# servo_1.net
KiCad netlist of a schematic drawn in EAGLE
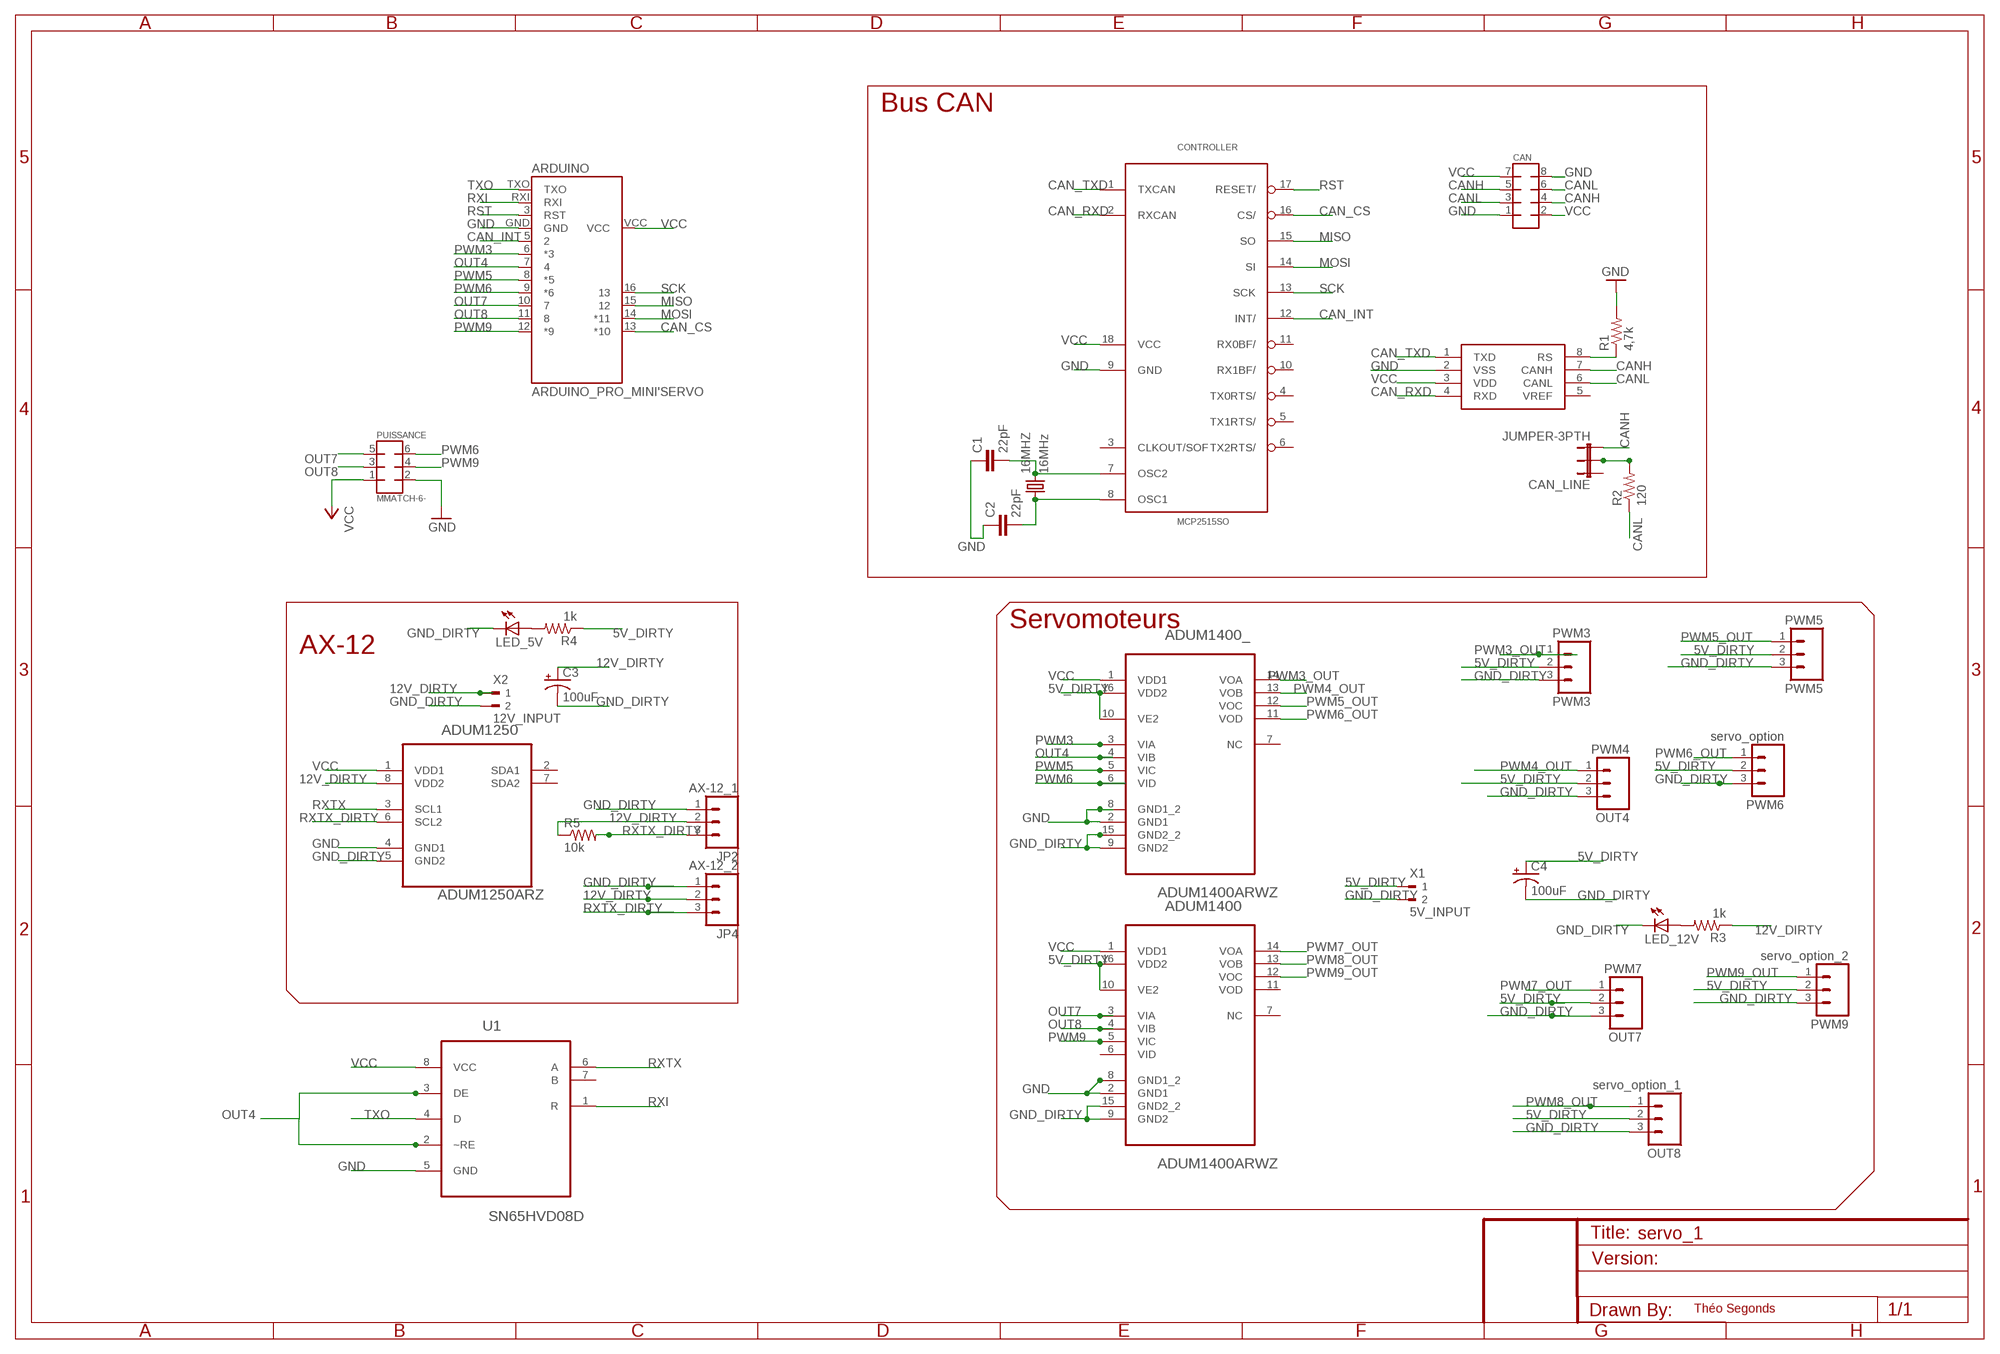
[diagram p0: schematic, sheet 1]

(export (version "E")
  (design (tool "Eeschema 10.0.6"))
  (components
    (comp (ref "16MHZ")
      (value "16MHz")
      (footprint "eagle-import:HC49_S")
      (fields (field (name "MF") "MULTICOMP") (field (name "MPN") "HC49SM-3.6864-30-50-60-16-ATF"))
      (libsource (lib "eagle-import") (part "CRYSTALHC49S"))
    )
    (comp (ref "ADUM1250")
      (value "ADUM1250ARZ")
      (footprint "eagle-import:SOIC127P600X175-8N")
      (fields (field (name "MF") "ANALOG DEVICES"))
      (libsource (lib "eagle-import") (part "ADUM1250ARZ"))
    )
    (comp (ref "ADUM1400")
      (value "ADUM1400ARWZ")
      (footprint "eagle-import:SOIC127P1032X265-16N")
      (fields (field (name "MF") "ANALOG DEVICES"))
      (libsource (lib "eagle-import") (part "ADUM1400ARWZ"))
    )
    (comp (ref "ADUM1400_")
      (value "ADUM1400ARWZ")
      (footprint "eagle-import:SOIC127P1032X265-16N")
      (fields (field (name "MF") "ANALOG DEVICES"))
      (libsource (lib "eagle-import") (part "ADUM1400ARWZ"))
    )
    (comp (ref "ARDUINO")
      (value "ARDUINO_PRO_MINI'SERVO")
      (footprint "eagle-import:ARDUINO_PRO_MINI")
      (libsource (lib "eagle-import") (part "ARDUINO_PRO_MINI'SERVO"))
    )
    (comp (ref "C1")
      (value "22pF")
      (footprint "eagle-import:0805")
      (fields (field (name "MF") "AVX") (field (name "MPN") "08055A220JAT2A"))
      (libsource (lib "eagle-import") (part "CAP0805"))
    )
    (comp (ref "C2")
      (value "22pF")
      (footprint "eagle-import:0805")
      (fields (field (name "MF") "AVX") (field (name "MPN") "08055A220JAT2A"))
      (libsource (lib "eagle-import") (part "CAP0805"))
    )
    (comp (ref "C3")
      (value "100uF")
      (footprint "eagle-import:CPOL-RADIAL-100UF-25V")
      (fields (field (name "MF") "RUBYCON") (field (name "MPN") "100TXW100MEFC8X30"))
      (libsource (lib "eagle-import") (part "CAP_POLPTH1"))
    )
    (comp (ref "C4")
      (value "100uF")
      (footprint "eagle-import:CPOL-RADIAL-100UF-25V")
      (fields (field (name "MF") "RUBYCON") (field (name "MPN") "100TXW100MEFC8X30"))
      (libsource (lib "eagle-import") (part "CAP_POLPTH1"))
    )
    (comp (ref "CAN")
      (value "MMATCH-8-PTH")
      (footprint "eagle-import:AMP-215079-8")
      (libsource (lib "eagle-import") (part "MMATCH-8-PTH"))
    )
    (comp (ref "CAN_LINE")
      (value "JUMPER-3PTH")
      (footprint "eagle-import:1X03")
      (libsource (lib "eagle-import") (part "JUMPER-3PTH"))
    )
    (comp (ref "CONTROLLER")
      (value "MCP2515SO")
      (footprint "eagle-import:SO18L")
      (libsource (lib "eagle-import") (part "MCP2515SO"))
    )
    (comp (ref "JP2")
      (value "AX-12_1")
      (footprint "eagle-import:MOLEX-1X3")
      (libsource (lib "eagle-import") (part "M03POLAR"))
    )
    (comp (ref "JP4")
      (value "AX-12_2")
      (footprint "eagle-import:MOLEX-1X3")
      (libsource (lib "eagle-import") (part "M03POLAR"))
    )
    (comp (ref "LED_5V")
      (value "LEDCHIPLED_0805")
      (footprint "eagle-import:CHIPLED_0805")
      (libsource (lib "eagle-import") (part "LEDCHIPLED_0805"))
    )
    (comp (ref "LED_12V")
      (value "LEDCHIPLED_0805")
      (footprint "eagle-import:CHIPLED_0805")
      (libsource (lib "eagle-import") (part "LEDCHIPLED_0805"))
    )
    (comp (ref "OUT4")
      (value "PWM4")
      (footprint "eagle-import:1X03")
      (libsource (lib "eagle-import") (part "M03PTH"))
    )
    (comp (ref "OUT7")
      (value "PWM7")
      (footprint "eagle-import:1X03")
      (libsource (lib "eagle-import") (part "M03PTH"))
    )
    (comp (ref "OUT8")
      (value "servo_option_1")
      (footprint "eagle-import:1X03")
      (libsource (lib "eagle-import") (part "M03PTH"))
    )
    (comp (ref "PUISSANCE")
      (value "MMATCH-6-")
      (footprint "eagle-import:AMP-215079-6")
      (libsource (lib "eagle-import") (part "MMATCH-6-"))
    )
    (comp (ref "PWM3")
      (value "PWM3")
      (footprint "eagle-import:1X03")
      (libsource (lib "eagle-import") (part "M03PTH"))
    )
    (comp (ref "PWM5")
      (value "PWM5")
      (footprint "eagle-import:1X03")
      (libsource (lib "eagle-import") (part "M03PTH"))
    )
    (comp (ref "PWM6")
      (value "servo_option")
      (footprint "eagle-import:1X03")
      (libsource (lib "eagle-import") (part "M03PTH"))
    )
    (comp (ref "PWM9")
      (value "servo_option_2")
      (footprint "eagle-import:1X03")
      (libsource (lib "eagle-import") (part "M03PTH"))
    )
    (comp (ref "R1")
      (value "4,7k")
      (footprint "eagle-import:0805")
      (libsource (lib "eagle-import") (part "RESISTOR0805-RES"))
    )
    (comp (ref "R2")
      (value "120")
      (footprint "eagle-import:0805")
      (libsource (lib "eagle-import") (part "RESISTOR0805-RES"))
    )
    (comp (ref "R3")
      (value "1k")
      (footprint "eagle-import:0805")
      (libsource (lib "eagle-import") (part "RESISTOR0805-RES"))
    )
    (comp (ref "R4")
      (value "1k")
      (footprint "eagle-import:0805")
      (libsource (lib "eagle-import") (part "RESISTOR0805-RES"))
    )
    (comp (ref "R5")
      (value "10k")
      (footprint "eagle-import:0805")
      (libsource (lib "eagle-import") (part "RESISTOR0805-RES"))
    )
    (comp (ref "TRANSCEIVER")
      (value "MCP2551")
      (footprint "eagle-import:SO08")
      (fields (field (name "MF") "MICROCHIP") (field (name "MPN") "MCP2551-I/SN..."))
      (libsource (lib "eagle-import") (part "MCP2551"))
    )
    (comp (ref "U1")
      (value "SN65HVD08D")
      (footprint "eagle-import:SOIC127P600X175-8N")
      (libsource (lib "eagle-import") (part "SN65HVD08D"))
    )
    (comp (ref "X1")
      (value "5V_INPUT")
      (footprint "eagle-import:90-2")
      (libsource (lib "eagle-import") (part "90-2"))
    )
    (comp (ref "X2")
      (value "12V_INPUT")
      (footprint "eagle-import:90-2")
      (libsource (lib "eagle-import") (part "90-2"))
    )
  )
  (nets
    (net (code "1") (name "/5V_DIRTY") (class "Default")
      (node (ref "ADUM1400") (pin "10") (pinfunction "VE2_10") (pintype "input"))
      (node (ref "ADUM1400") (pin "16") (pinfunction "VDD2_16") (pintype "power_in"))
      (node (ref "ADUM1400_") (pin "10") (pinfunction "VE2_10") (pintype "input"))
      (node (ref "ADUM1400_") (pin "16") (pinfunction "VDD2_16") (pintype "power_in"))
      (node (ref "C4") (pin "1") (pinfunction "+_1") (pintype "passive"))
      (node (ref "OUT4") (pin "2") (pinfunction "2_2") (pintype "passive"))
      (node (ref "OUT7") (pin "2") (pinfunction "2_2") (pintype "passive"))
      (node (ref "OUT8") (pin "2") (pinfunction "2_2") (pintype "passive"))
      (node (ref "PWM3") (pin "2") (pinfunction "2_2") (pintype "passive"))
      (node (ref "PWM5") (pin "2") (pinfunction "2_2") (pintype "passive"))
      (node (ref "PWM6") (pin "2") (pinfunction "2_2") (pintype "passive"))
      (node (ref "PWM9") (pin "2") (pinfunction "2_2") (pintype "passive"))
      (node (ref "R4") (pin "1") (pinfunction "1_1") (pintype "passive"))
      (node (ref "X1") (pin "1") (pinfunction "1_1") (pintype "passive"))
    )
    (net (code "2") (name "/12V_DIRTY") (class "Default")
      (node (ref "ADUM1250") (pin "8") (pinfunction "VDD2_8") (pintype "power_in"))
      (node (ref "C3") (pin "1") (pinfunction "+_1") (pintype "passive"))
      (node (ref "JP2") (pin "2") (pinfunction "2_2") (pintype "passive"))
      (node (ref "JP4") (pin "2") (pinfunction "2_2") (pintype "passive"))
      (node (ref "R3") (pin "1") (pinfunction "1_1") (pintype "passive"))
      (node (ref "R5") (pin "1") (pinfunction "1_1") (pintype "passive"))
      (node (ref "X2") (pin "1") (pinfunction "1_1") (pintype "passive"))
    )
    (net (code "3") (name "/CANH") (class "Default")
      (node (ref "CAN") (pin "4") (pinfunction "4_4") (pintype "bidirectional"))
      (node (ref "CAN") (pin "5") (pinfunction "5_5") (pintype "bidirectional"))
      (node (ref "CAN_LINE") (pin "3") (pinfunction "3_3") (pintype "passive"))
      (node (ref "TRANSCEIVER") (pin "7") (pinfunction "CANH_7") (pintype "bidirectional"))
    )
    (net (code "4") (name "/CANL") (class "Default")
      (node (ref "CAN") (pin "3") (pinfunction "3_3") (pintype "bidirectional"))
      (node (ref "CAN") (pin "6") (pinfunction "6_6") (pintype "bidirectional"))
      (node (ref "R2") (pin "1") (pinfunction "1_1") (pintype "passive"))
      (node (ref "TRANSCEIVER") (pin "6") (pinfunction "CANL_6") (pintype "bidirectional"))
    )
    (net (code "5") (name "/CAN_CS") (class "Default")
      (node (ref "ARDUINO") (pin "13") (pinfunction "*10_13") (pintype "bidirectional"))
      (node (ref "CONTROLLER") (pin "16") (pinfunction "CS/_16") (pintype "input"))
    )
    (net (code "6") (name "/CAN_INT") (class "Default")
      (node (ref "ARDUINO") (pin "5") (pinfunction "2_5") (pintype "bidirectional"))
      (node (ref "CONTROLLER") (pin "12") (pinfunction "INT/_12") (pintype "output"))
    )
    (net (code "7") (name "/CAN_RXD") (class "Default")
      (node (ref "CONTROLLER") (pin "2") (pinfunction "RXCAN_2") (pintype "input"))
      (node (ref "TRANSCEIVER") (pin "4") (pinfunction "RXD_4") (pintype "bidirectional"))
    )
    (net (code "8") (name "/CAN_TXD") (class "Default")
      (node (ref "CONTROLLER") (pin "1") (pinfunction "TXCAN_1") (pintype "output"))
      (node (ref "TRANSCEIVER") (pin "1") (pinfunction "TXD_1") (pintype "bidirectional"))
    )
    (net (code "9") (name "/GND_DIRTY") (class "Default")
      (node (ref "ADUM1250") (pin "5") (pinfunction "GND2_5") (pintype "passive"))
      (node (ref "ADUM1400") (pin "15") (pinfunction "GND2_2_15") (pintype "passive"))
      (node (ref "ADUM1400") (pin "9") (pinfunction "GND2_9") (pintype "passive"))
      (node (ref "ADUM1400_") (pin "15") (pinfunction "GND2_2_15") (pintype "passive"))
      (node (ref "ADUM1400_") (pin "9") (pinfunction "GND2_9") (pintype "passive"))
      (node (ref "C3") (pin "2") (pinfunction "-_2") (pintype "passive"))
      (node (ref "C4") (pin "2") (pinfunction "-_2") (pintype "passive"))
      (node (ref "JP2") (pin "1") (pinfunction "1_1") (pintype "passive"))
      (node (ref "JP4") (pin "1") (pinfunction "1_1") (pintype "passive"))
      (node (ref "LED_12V") (pin "C") (pinfunction "C_C") (pintype "passive"))
      (node (ref "LED_5V") (pin "C") (pinfunction "C_C") (pintype "passive"))
      (node (ref "OUT4") (pin "3") (pinfunction "3_3") (pintype "passive"))
      (node (ref "OUT7") (pin "3") (pinfunction "3_3") (pintype "passive"))
      (node (ref "OUT8") (pin "3") (pinfunction "3_3") (pintype "passive"))
      (node (ref "PWM3") (pin "3") (pinfunction "3_3") (pintype "passive"))
      (node (ref "PWM5") (pin "3") (pinfunction "3_3") (pintype "passive"))
      (node (ref "PWM6") (pin "3") (pinfunction "3_3") (pintype "passive"))
      (node (ref "PWM9") (pin "3") (pinfunction "3_3") (pintype "passive"))
      (node (ref "X1") (pin "2") (pinfunction "2_2") (pintype "passive"))
      (node (ref "X2") (pin "2") (pinfunction "2_2") (pintype "passive"))
    )
    (net (code "10") (name "/MISO") (class "Default")
      (node (ref "ARDUINO") (pin "15") (pinfunction "12_15") (pintype "bidirectional"))
      (node (ref "CONTROLLER") (pin "15") (pinfunction "SO_15") (pintype "output"))
    )
    (net (code "11") (name "/MOSI") (class "Default")
      (node (ref "ARDUINO") (pin "14") (pinfunction "*11_14") (pintype "bidirectional"))
      (node (ref "CONTROLLER") (pin "14") (pinfunction "SI_14") (pintype "input"))
    )
    (net (code "12") (name "/OUT4") (class "Default")
      (node (ref "ADUM1400_") (pin "4") (pinfunction "VIB_4") (pintype "input"))
      (node (ref "ARDUINO") (pin "7") (pinfunction "4_7") (pintype "bidirectional"))
      (node (ref "U1") (pin "2") (pinfunction "~{RE}_2") (pintype "input"))
      (node (ref "U1") (pin "3") (pinfunction "DE_3") (pintype "input"))
    )
    (net (code "13") (name "/OUT7") (class "Default")
      (node (ref "ADUM1400") (pin "3") (pinfunction "VIA_3") (pintype "input"))
      (node (ref "ARDUINO") (pin "10") (pinfunction "7_10") (pintype "bidirectional"))
      (node (ref "PUISSANCE") (pin "5") (pinfunction "7_5") (pintype "bidirectional"))
    )
    (net (code "14") (name "/OUT8") (class "Default")
      (node (ref "ADUM1400") (pin "4") (pinfunction "VIB_4") (pintype "input"))
      (node (ref "ARDUINO") (pin "11") (pinfunction "8_11") (pintype "bidirectional"))
      (node (ref "PUISSANCE") (pin "3") (pinfunction "5_3") (pintype "bidirectional"))
    )
    (net (code "15") (name "/PWM3") (class "Default")
      (node (ref "ADUM1400_") (pin "3") (pinfunction "VIA_3") (pintype "input"))
      (node (ref "ARDUINO") (pin "6") (pinfunction "*3_6") (pintype "bidirectional"))
    )
    (net (code "16") (name "/PWM3_OUT") (class "Default")
      (node (ref "ADUM1400_") (pin "14") (pinfunction "VOA_14") (pintype "output"))
      (node (ref "PWM3") (pin "1") (pinfunction "1_1") (pintype "passive"))
    )
    (net (code "17") (name "/PWM4_OUT") (class "Default")
      (node (ref "ADUM1400_") (pin "13") (pinfunction "VOB_13") (pintype "output"))
      (node (ref "OUT4") (pin "1") (pinfunction "1_1") (pintype "passive"))
    )
    (net (code "18") (name "/PWM5") (class "Default")
      (node (ref "ADUM1400_") (pin "5") (pinfunction "VIC_5") (pintype "input"))
      (node (ref "ARDUINO") (pin "8") (pinfunction "*5_8") (pintype "bidirectional"))
    )
    (net (code "19") (name "/PWM5_OUT") (class "Default")
      (node (ref "ADUM1400_") (pin "12") (pinfunction "VOC_12") (pintype "output"))
      (node (ref "PWM5") (pin "1") (pinfunction "1_1") (pintype "passive"))
    )
    (net (code "20") (name "/PWM6") (class "Default")
      (node (ref "ADUM1400_") (pin "6") (pinfunction "VID_6") (pintype "input"))
      (node (ref "ARDUINO") (pin "9") (pinfunction "*6_9") (pintype "bidirectional"))
      (node (ref "PUISSANCE") (pin "6") (pinfunction "8_6") (pintype "bidirectional"))
    )
    (net (code "21") (name "/PWM6_OUT") (class "Default")
      (node (ref "ADUM1400_") (pin "11") (pinfunction "VOD_11") (pintype "output"))
      (node (ref "PWM6") (pin "1") (pinfunction "1_1") (pintype "passive"))
    )
    (net (code "22") (name "/PWM7_OUT") (class "Default")
      (node (ref "ADUM1400") (pin "14") (pinfunction "VOA_14") (pintype "output"))
      (node (ref "OUT7") (pin "1") (pinfunction "1_1") (pintype "passive"))
    )
    (net (code "23") (name "/PWM8_OUT") (class "Default")
      (node (ref "ADUM1400") (pin "13") (pinfunction "VOB_13") (pintype "output"))
      (node (ref "OUT8") (pin "1") (pinfunction "1_1") (pintype "passive"))
    )
    (net (code "24") (name "/PWM9") (class "Default")
      (node (ref "ADUM1400") (pin "5") (pinfunction "VIC_5") (pintype "input"))
      (node (ref "ARDUINO") (pin "12") (pinfunction "*9_12") (pintype "bidirectional"))
      (node (ref "PUISSANCE") (pin "4") (pinfunction "6_4") (pintype "bidirectional"))
    )
    (net (code "25") (name "/PWM9_OUT") (class "Default")
      (node (ref "ADUM1400") (pin "12") (pinfunction "VOC_12") (pintype "output"))
      (node (ref "PWM9") (pin "1") (pinfunction "1_1") (pintype "passive"))
    )
    (net (code "26") (name "/RST") (class "Default")
      (node (ref "ARDUINO") (pin "3") (pinfunction "RST_3") (pintype "bidirectional"))
      (node (ref "CONTROLLER") (pin "17") (pinfunction "RESET/_17") (pintype "input"))
    )
    (net (code "27") (name "/RXI") (class "Default")
      (node (ref "ARDUINO") (pin "RXI") (pinfunction "RXI_RXI") (pintype "bidirectional"))
      (node (ref "U1") (pin "1") (pinfunction "R_1") (pintype "output"))
    )
    (net (code "28") (name "/RXTX") (class "Default")
      (node (ref "ADUM1250") (pin "3") (pinfunction "SCL1_3") (pintype "input"))
      (node (ref "U1") (pin "6") (pinfunction "A_6") (pintype "output"))
    )
    (net (code "29") (name "/RXTX_DIRTY") (class "Default")
      (node (ref "ADUM1250") (pin "6") (pinfunction "SCL2_6") (pintype "input"))
      (node (ref "JP2") (pin "3") (pinfunction "3_3") (pintype "passive"))
      (node (ref "JP4") (pin "3") (pinfunction "3_3") (pintype "passive"))
      (node (ref "R5") (pin "2") (pinfunction "2_2") (pintype "passive"))
    )
    (net (code "30") (name "/SCK") (class "Default")
      (node (ref "ARDUINO") (pin "16") (pinfunction "13_16") (pintype "bidirectional"))
      (node (ref "CONTROLLER") (pin "13") (pinfunction "SCK_13") (pintype "input"))
    )
    (net (code "31") (name "/TXO") (class "Default")
      (node (ref "ARDUINO") (pin "TXO") (pinfunction "TXO_TXO") (pintype "bidirectional"))
      (node (ref "U1") (pin "4") (pinfunction "D_4") (pintype "input"))
    )
    (net (code "32") (name "GND") (class "Default")
      (node (ref "ADUM1250") (pin "4") (pinfunction "GND1_4") (pintype "passive"))
      (node (ref "ADUM1400") (pin "2") (pinfunction "GND1_2") (pintype "passive"))
      (node (ref "ADUM1400") (pin "8") (pinfunction "GND1_2_8") (pintype "passive"))
      (node (ref "ADUM1400_") (pin "2") (pinfunction "GND1_2") (pintype "passive"))
      (node (ref "ADUM1400_") (pin "8") (pinfunction "GND1_2_8") (pintype "passive"))
      (node (ref "ARDUINO") (pin "GND") (pinfunction "GND_GND") (pintype "bidirectional"))
      (node (ref "C1") (pin "1") (pinfunction "1_1") (pintype "passive"))
      (node (ref "C2") (pin "1") (pinfunction "1_1") (pintype "passive"))
      (node (ref "CAN") (pin "1") (pinfunction "1_1") (pintype "bidirectional"))
      (node (ref "CAN") (pin "8") (pinfunction "8_8") (pintype "bidirectional"))
      (node (ref "CONTROLLER") (pin "9") (pinfunction "GND_9") (pintype "power_in"))
      (node (ref "PUISSANCE") (pin "2") (pinfunction "4_2") (pintype "bidirectional"))
      (node (ref "R1") (pin "2") (pinfunction "2_2") (pintype "passive"))
      (node (ref "TRANSCEIVER") (pin "2") (pinfunction "VSS_2") (pintype "bidirectional"))
      (node (ref "U1") (pin "5") (pinfunction "GND_5") (pintype "passive"))
    )
    (net (code "33") (name "Net-(CAN_LINE-Pad2)") (class "Default")
      (node (ref "CAN_LINE") (pin "2") (pinfunction "2_2") (pintype "passive"))
      (node (ref "R2") (pin "2") (pinfunction "2_2") (pintype "passive"))
    )
    (net (code "34") (name "Net-(CONTROLLER-OSC1)") (class "Default")
      (node (ref "16MHZ") (pin "1") (pinfunction "1_1") (pintype "passive"))
      (node (ref "C2") (pin "2") (pinfunction "2_2") (pintype "passive"))
      (node (ref "CONTROLLER") (pin "8") (pinfunction "OSC1_8") (pintype "bidirectional"))
    )
    (net (code "35") (name "Net-(CONTROLLER-OSC2)") (class "Default")
      (node (ref "16MHZ") (pin "2") (pinfunction "2_2") (pintype "passive"))
      (node (ref "C1") (pin "2") (pinfunction "2_2") (pintype "passive"))
      (node (ref "CONTROLLER") (pin "7") (pinfunction "OSC2_7") (pintype "bidirectional"))
    )
    (net (code "36") (name "Net-(LED_5V-PadA)") (class "Default")
      (node (ref "LED_5V") (pin "A") (pinfunction "A_A") (pintype "passive"))
      (node (ref "R4") (pin "2") (pinfunction "2_2") (pintype "passive"))
    )
    (net (code "37") (name "Net-(LED_12V-PadA)") (class "Default")
      (node (ref "LED_12V") (pin "A") (pinfunction "A_A") (pintype "passive"))
      (node (ref "R3") (pin "2") (pinfunction "2_2") (pintype "passive"))
    )
    (net (code "38") (name "Net-(TRANSCEIVER-RS)") (class "Default")
      (node (ref "R1") (pin "1") (pinfunction "1_1") (pintype "passive"))
      (node (ref "TRANSCEIVER") (pin "8") (pinfunction "RS_8") (pintype "bidirectional"))
    )
    (net (code "39") (name "VCC") (class "Default")
      (node (ref "ADUM1250") (pin "1") (pinfunction "VDD1_1") (pintype "power_in"))
      (node (ref "ADUM1400") (pin "1") (pinfunction "VDD1_1") (pintype "power_in"))
      (node (ref "ADUM1400_") (pin "1") (pinfunction "VDD1_1") (pintype "power_in"))
      (node (ref "ARDUINO") (pin "VCC") (pinfunction "VCC_VCC") (pintype "bidirectional"))
      (node (ref "CAN") (pin "2") (pinfunction "2_2") (pintype "bidirectional"))
      (node (ref "CAN") (pin "7") (pinfunction "7_7") (pintype "bidirectional"))
      (node (ref "CONTROLLER") (pin "18") (pinfunction "VCC_18") (pintype "power_in"))
      (node (ref "PUISSANCE") (pin "1") (pinfunction "3_1") (pintype "bidirectional"))
      (node (ref "TRANSCEIVER") (pin "3") (pinfunction "VDD_3") (pintype "bidirectional"))
      (node (ref "U1") (pin "8") (pinfunction "VCC_8") (pintype "power_in"))
    )
    (net (code "40") (name "unconnected-(ADUM1250-SDA1-Pad2)") (class "Default")
      (node (ref "ADUM1250") (pin "2") (pinfunction "SDA1_2") (pintype "bidirectional"))
    )
    (net (code "41") (name "unconnected-(ADUM1250-SDA2-Pad7)") (class "Default")
      (node (ref "ADUM1250") (pin "7") (pinfunction "SDA2_7") (pintype "bidirectional"))
    )
    (net (code "42") (name "unconnected-(ADUM1400-NC-Pad7)") (class "Default")
      (node (ref "ADUM1400") (pin "7") (pinfunction "NC_7") (pintype "no_connect"))
    )
    (net (code "43") (name "unconnected-(ADUM1400-VID-Pad6)") (class "Default")
      (node (ref "ADUM1400") (pin "6") (pinfunction "VID_6") (pintype "input"))
    )
    (net (code "44") (name "unconnected-(ADUM1400-VOD-Pad11)") (class "Default")
      (node (ref "ADUM1400") (pin "11") (pinfunction "VOD_11") (pintype "output"))
    )
    (net (code "45") (name "unconnected-(ADUM1400_-NC-Pad7)") (class "Default")
      (node (ref "ADUM1400_") (pin "7") (pinfunction "NC_7") (pintype "no_connect"))
    )
    (net (code "46") (name "unconnected-(CAN_LINE-Pad1)") (class "Default")
      (node (ref "CAN_LINE") (pin "1") (pinfunction "1_1") (pintype "passive"))
    )
    (net (code "47") (name "unconnected-(CONTROLLER-CLKOUT{slash}SOF-Pad3)") (class "Default")
      (node (ref "CONTROLLER") (pin "3") (pinfunction "CLKOUT/SOF_3") (pintype "bidirectional"))
    )
    (net (code "48") (name "unconnected-(CONTROLLER-RX0BF{slash}-Pad11)") (class "Default")
      (node (ref "CONTROLLER") (pin "11") (pinfunction "RX0BF/_11") (pintype "bidirectional"))
    )
    (net (code "49") (name "unconnected-(CONTROLLER-RX1BF{slash}-Pad10)") (class "Default")
      (node (ref "CONTROLLER") (pin "10") (pinfunction "RX1BF/_10") (pintype "bidirectional"))
    )
    (net (code "50") (name "unconnected-(CONTROLLER-TX0RTS{slash}-Pad4)") (class "Default")
      (node (ref "CONTROLLER") (pin "4") (pinfunction "TX0RTS/_4") (pintype "bidirectional"))
    )
    (net (code "51") (name "unconnected-(CONTROLLER-TX1RTS{slash}-Pad5)") (class "Default")
      (node (ref "CONTROLLER") (pin "5") (pinfunction "TX1RTS/_5") (pintype "bidirectional"))
    )
    (net (code "52") (name "unconnected-(CONTROLLER-TX2RTS{slash}-Pad6)") (class "Default")
      (node (ref "CONTROLLER") (pin "6") (pinfunction "TX2RTS/_6") (pintype "bidirectional"))
    )
    (net (code "53") (name "unconnected-(TRANSCEIVER-VREF-Pad5)") (class "Default")
      (node (ref "TRANSCEIVER") (pin "5") (pinfunction "VREF_5") (pintype "bidirectional"))
    )
    (net (code "54") (name "unconnected-(U1-B-Pad7)") (class "Default")
      (node (ref "U1") (pin "7") (pinfunction "B_7") (pintype "output"))
    )
  )
)
